# Alimentation.net
KiCad netlist of a schematic drawn in Altium Designer
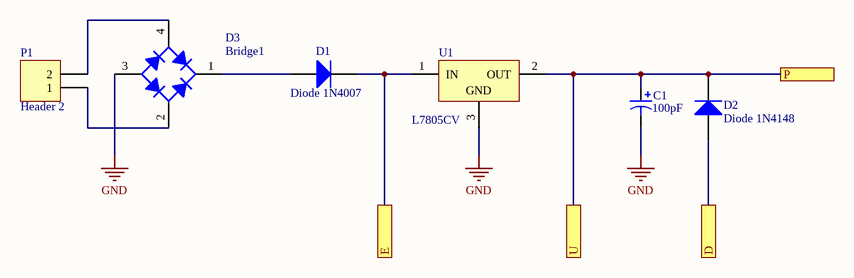
[diagram p0: Alimentation.SchDoc]

(export (version "E")
  (design (tool "Eeschema 10.0.6"))
  (components
    (comp (ref "C1")
      (value "100pF")
      (footprint "RB7.6-15")
      (description "Polarized Capacitor (Radial)")
      (fields (field (name "Comment") "Cap Pol1") (field (name "PUBLISHER") "Altium Limited"))
      (libsource (lib "Miscellaneous Devices") (part "Cap Pol1"))
    )
    (comp (ref "D1")
      (value "Diode 1N4007")
      (footprint "DO-41")
      (description "1 Amp General Purpose Rectifier")
      (fields (field (name "PUBLISHER") "Altium Limited"))
      (libsource (lib "Miscellaneous Devices") (part "Diode 1N4007"))
    )
    (comp (ref "D2")
      (value "Diode 1N4148")
      (footprint "DO-35")
      (description "High Conductance Fast Diode")
      (fields (field (name "PUBLISHER") "Altium Limited"))
      (libsource (lib "Miscellaneous Devices") (part "Diode 1N4148"))
    )
    (comp (ref "D3")
      (value "Bridge1")
      (footprint "D-38")
      (description "Full Wave Diode Bridge")
      (fields (field (name "PUBLISHER") "Altium Limited"))
      (libsource (lib "Miscellaneous Devices") (part "Bridge1"))
    )
    (comp (ref "P1")
      (value "Header 2")
      (footprint "HDR1X2")
      (description "Header, 2-Pin")
      (fields (field (name "PUBLISHER") "Altium Limited"))
      (libsource (lib "Miscellaneous Connectors") (part "Header 2"))
    )
    (comp (ref "U1")
      (value "L7805CV")
      (footprint "TO220ABN")
      (description "Positive Voltage Regulator")
      (fields (field (name "PUBLISHER") "Altium Limited"))
      (libsource (lib "ST Power Mgt Voltage Regulator") (part "L7805CV"))
    )
  )
  (nets
    (net (code "1") (name "/D") (class "Default")
      (node (ref "D2") (pin "1") (pinfunction "A_1") (pintype "passive"))
    )
    (net (code "2") (name "/E") (class "Default")
      (node (ref "D1") (pin "2") (pinfunction "K_2") (pintype "passive"))
      (node (ref "U1") (pin "1") (pinfunction "IN_1") (pintype "power_in"))
    )
    (net (code "3") (name "/P") (class "Default")
      (node (ref "C1") (pin "1") (pinfunction "1_1") (pintype "passive"))
      (node (ref "D2") (pin "2") (pinfunction "K_2") (pintype "passive"))
      (node (ref "U1") (pin "2") (pinfunction "OUT_2") (pintype "power_in"))
    )
    (net (code "4") (name "GND") (class "Default")
      (node (ref "C1") (pin "2") (pinfunction "2_2") (pintype "passive"))
      (node (ref "D3") (pin "3") (pinfunction "A_3") (pintype "passive"))
      (node (ref "U1") (pin "3") (pinfunction "GND_3") (pintype "power_in"))
    )
    (net (code "5") (name "Net-(D1-A)") (class "Default")
      (node (ref "D1") (pin "1") (pinfunction "A_1") (pintype "passive"))
      (node (ref "D3") (pin "1") (pinfunction "K_1") (pintype "passive"))
    )
    (net (code "6") (name "Net-(D3-C-Pad2)") (class "Default")
      (node (ref "D3") (pin "2") (pinfunction "C_2") (pintype "passive"))
      (node (ref "P1") (pin "1") (pinfunction "1_1") (pintype "passive"))
    )
    (net (code "7") (name "Net-(D3-C-Pad4)") (class "Default")
      (node (ref "D3") (pin "4") (pinfunction "C_4") (pintype "passive"))
      (node (ref "P1") (pin "2") (pinfunction "2_2") (pintype "passive"))
    )
  )
)
